# RTD_Sesnor.net
KiCad netlist of a schematic drawn in EAGLE
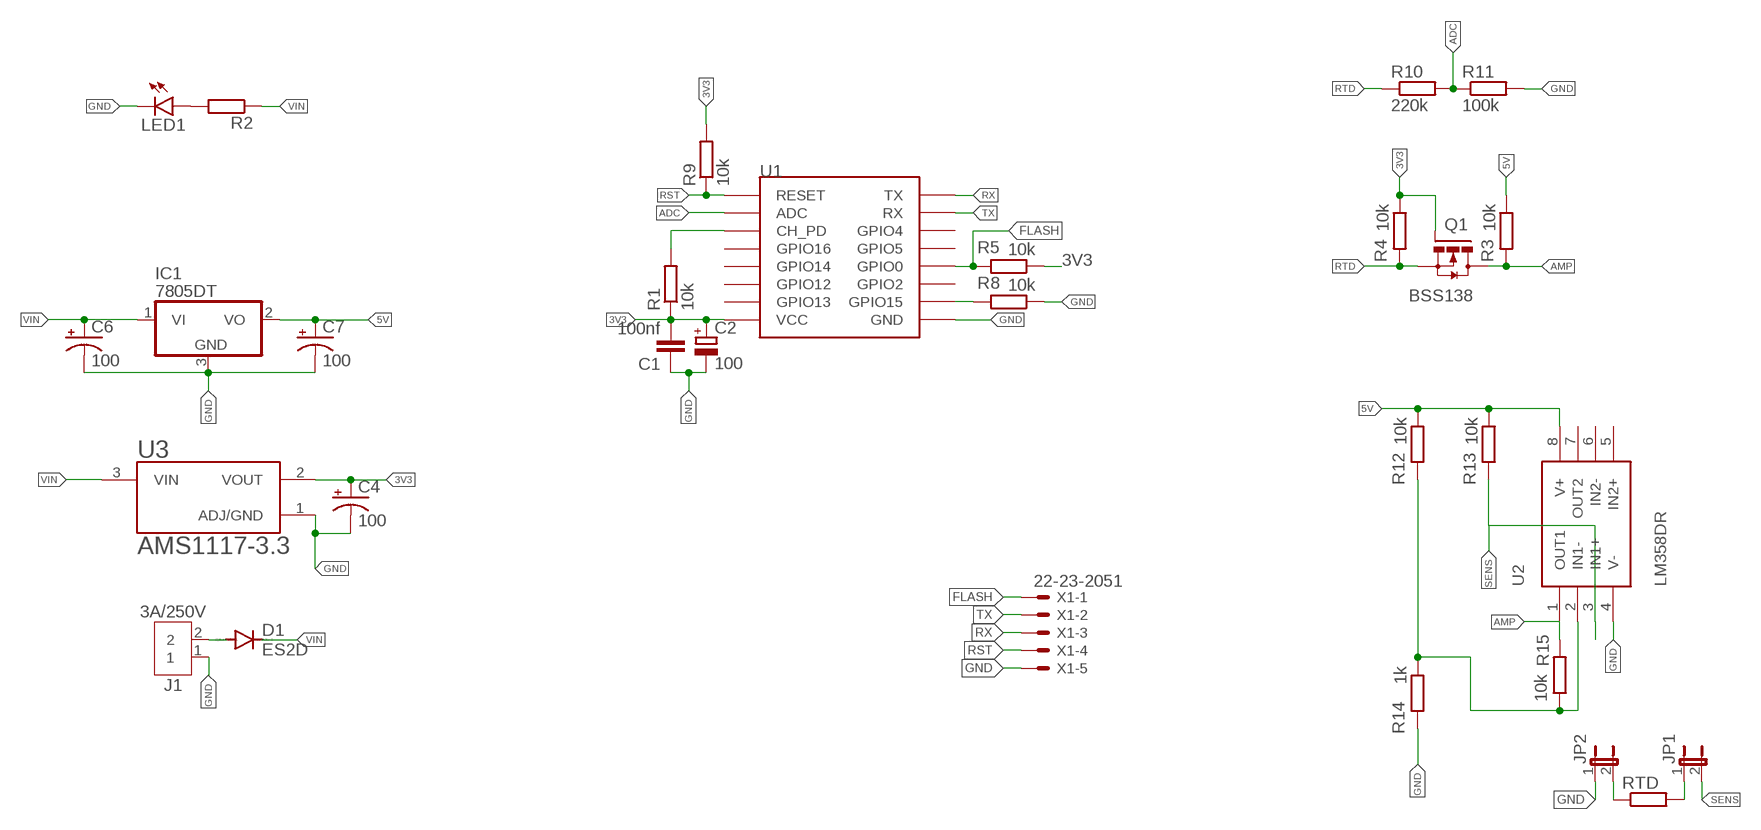
[diagram p0: schematic, sheet 1]

(export (version "E")
  (design (tool "Eeschema 10.0.6"))
  (components
    (comp (ref "C1")
      (value "100nf")
      (footprint "eagle-import:C0805K")
      (libsource (lib "eagle-import") (part "C-EUC0805K"))
    )
    (comp (ref "C2")
      (value "100")
      (footprint "eagle-import:153CLV-0605")
      (libsource (lib "eagle-import") (part "CPOL-EU153CLV-0605"))
    )
    (comp (ref "C4")
      (value "100")
      (footprint "eagle-import:153CLV-0605")
      (libsource (lib "eagle-import") (part "CPOL-US153CLV-0605"))
    )
    (comp (ref "C6")
      (value "100")
      (footprint "eagle-import:153CLV-0605")
      (libsource (lib "eagle-import") (part "CPOL-US153CLV-0605"))
    )
    (comp (ref "C7")
      (value "100")
      (footprint "eagle-import:153CLV-0605")
      (libsource (lib "eagle-import") (part "CPOL-US153CLV-0605"))
    )
    (comp (ref "D1")
      (value "ES2D")
      (footprint "eagle-import:SMB")
      (libsource (lib "eagle-import") (part "ES2D"))
    )
    (comp (ref "IC1")
      (value "7805DT")
      (footprint "eagle-import:TO252")
      (libsource (lib "eagle-import") (part "78DT05"))
    )
    (comp (ref "J1")
      (value "3A/250V")
      (footprint "eagle-import:B2B-XH-A")
      (fields (field (name "MANUFACTURER") "JST (XH CONNECTOR)") (field (name "MPN") "B2B-XH-A"))
      (libsource (lib "eagle-import") (part "B2B-XH-A"))
    )
    (comp (ref "JP1")
      (value "JP1E")
      (footprint "eagle-import:JP1")
      (libsource (lib "eagle-import") (part "JP1E"))
    )
    (comp (ref "JP2")
      (value "JP1E")
      (footprint "eagle-import:JP1")
      (libsource (lib "eagle-import") (part "JP1E"))
    )
    (comp (ref "LED1")
      (value "LED3MM")
      (footprint "eagle-import:LED3MM")
      (libsource (lib "eagle-import") (part "LED3MM"))
    )
    (comp (ref "Q1")
      (value "BSS138")
      (footprint "eagle-import:SOT23-3")
      (fields
        (field (name "DIGIKEY_PART_NUMBER") "BSS138CT-ND")
        (field (name "MANUFACTURER") "ON Semiconductor")
        (field (name "CREATED_BY") "PCBLayout.com")
      )
      (libsource (lib "eagle-import") (part "BSS138"))
    )
    (comp (ref "R1")
      (value "10k")
      (footprint "eagle-import:R1206")
      (libsource (lib "eagle-import") (part "R-EU_R1206"))
    )
    (comp (ref "R2")
      (value "R-EU_R1206")
      (footprint "eagle-import:R1206")
      (libsource (lib "eagle-import") (part "R-EU_R1206"))
    )
    (comp (ref "R3")
      (value "10k")
      (footprint "eagle-import:R1206")
      (libsource (lib "eagle-import") (part "R-EU_R1206"))
    )
    (comp (ref "R4")
      (value "10k")
      (footprint "eagle-import:R1206")
      (libsource (lib "eagle-import") (part "R-EU_R1206"))
    )
    (comp (ref "R5")
      (value "10k")
      (footprint "eagle-import:R1206")
      (libsource (lib "eagle-import") (part "R-EU_R1206"))
    )
    (comp (ref "R8")
      (value "10k")
      (footprint "eagle-import:R1206")
      (libsource (lib "eagle-import") (part "R-EU_R1206"))
    )
    (comp (ref "R9")
      (value "10k")
      (footprint "eagle-import:R1206")
      (libsource (lib "eagle-import") (part "R-EU_R1206"))
    )
    (comp (ref "R10")
      (value "220k")
      (footprint "eagle-import:0204_7")
      (libsource (lib "eagle-import") (part "R-EU_0204/7"))
    )
    (comp (ref "R11")
      (value "100k")
      (footprint "eagle-import:0204_7")
      (libsource (lib "eagle-import") (part "R-EU_0204/7"))
    )
    (comp (ref "R12")
      (value "10k")
      (footprint "eagle-import:R1206")
      (libsource (lib "eagle-import") (part "R-EU_R1206"))
    )
    (comp (ref "R13")
      (value "10k")
      (footprint "eagle-import:R1206")
      (libsource (lib "eagle-import") (part "R-EU_R1206"))
    )
    (comp (ref "R14")
      (value "1k")
      (footprint "eagle-import:R1206")
      (libsource (lib "eagle-import") (part "R-EU_R1206"))
    )
    (comp (ref "R15")
      (value "10k")
      (footprint "eagle-import:R1206")
      (libsource (lib "eagle-import") (part "R-EU_R1206"))
    )
    (comp (ref "RTD")
      (value "R-EU_M0805")
      (footprint "eagle-import:M0805")
      (libsource (lib "eagle-import") (part "R-EU_M0805"))
    )
    (comp (ref "U1")
      (value "ESP12SMD")
      (footprint "eagle-import:ESP12-SMD")
      (libsource (lib "eagle-import") (part "ESP12SMD"))
    )
    (comp (ref "U2")
      (value "LM358DR")
      (footprint "eagle-import:LM358DR")
      (fields
        (field (name "DIGIKEY_PART_NUMBER") "296-1014-1-ND")
        (field (name "MANUFACTURER") "Texas Instruments")
        (field (name "CREATED_BY") "PCBLayout.com")
      )
      (libsource (lib "eagle-import") (part "LM358DR"))
    )
    (comp (ref "U3")
      (value "AMS1117-3.3")
      (footprint "eagle-import:SOT229P700X180-4N")
      (fields (field (name "MF") "Advanced Monolithic Systems"))
      (libsource (lib "eagle-import") (part "AMS1117-3.3"))
    )
    (comp (ref "X1")
      (value "22-23-2051")
      (footprint "eagle-import:22-23-2051")
      (fields (field (name "MF") "MOLEX"))
      (libsource (lib "eagle-import") (part "22-23-2051"))
    )
  )
  (nets
    (net (code "1") (name "3V3") (class "Default")
      (node (ref "C1") (pin "2") (pinfunction "2_2") (pintype "passive"))
      (node (ref "C2") (pin "+") (pinfunction "+_+") (pintype "passive"))
      (node (ref "C4") (pin "+") (pinfunction "+_+") (pintype "passive"))
      (node (ref "Q1") (pin "1") (pinfunction "G_1") (pintype "passive"))
      (node (ref "R1") (pin "1") (pinfunction "1_1") (pintype "passive"))
      (node (ref "R4") (pin "1") (pinfunction "1_1") (pintype "passive"))
      (node (ref "R5") (pin "1") (pinfunction "1_1") (pintype "passive"))
      (node (ref "R9") (pin "2") (pinfunction "2_2") (pintype "passive"))
      (node (ref "U1") (pin "VCC") (pinfunction "VCC_VCC") (pintype "bidirectional"))
      (node (ref "U3") (pin "2") (pinfunction "VOUT_2") (pintype "output"))
    )
    (net (code "2") (name "5V") (class "Default")
      (node (ref "C7") (pin "+") (pinfunction "+_+") (pintype "passive"))
      (node (ref "IC1") (pin "2") (pinfunction "VO_2") (pintype "passive"))
      (node (ref "R12") (pin "1") (pinfunction "1_1") (pintype "passive"))
      (node (ref "R13") (pin "1") (pinfunction "1_1") (pintype "passive"))
      (node (ref "R3") (pin "1") (pinfunction "1_1") (pintype "passive"))
      (node (ref "U2") (pin "8") (pinfunction "V+_8") (pintype "power_in"))
    )
    (net (code "3") (name "ADC") (class "Default")
      (node (ref "R10") (pin "2") (pinfunction "2_2") (pintype "passive"))
      (node (ref "R11") (pin "1") (pinfunction "1_1") (pintype "passive"))
      (node (ref "U1") (pin "ADC") (pinfunction "ADC_ADC") (pintype "bidirectional"))
    )
    (net (code "4") (name "AMP") (class "Default")
      (node (ref "Q1") (pin "3") (pinfunction "D_3") (pintype "passive"))
      (node (ref "R15") (pin "2") (pinfunction "2_2") (pintype "passive"))
      (node (ref "R3") (pin "2") (pinfunction "2_2") (pintype "passive"))
      (node (ref "U2") (pin "1") (pinfunction "OUT1_1") (pintype "output"))
    )
    (net (code "5") (name "FLASH") (class "Default")
      (node (ref "R5") (pin "2") (pinfunction "2_2") (pintype "passive"))
      (node (ref "U1") (pin "GPIO0") (pinfunction "GPIO0_GPIO0") (pintype "bidirectional"))
      (node (ref "X1") (pin "1") (pinfunction "S_1") (pintype "passive"))
    )
    (net (code "6") (name "GND") (class "Default")
      (node (ref "C1") (pin "1") (pinfunction "1_1") (pintype "passive"))
      (node (ref "C2") (pin "-") (pinfunction "-_-") (pintype "passive"))
      (node (ref "C4") (pin "-") (pinfunction "-_-") (pintype "passive"))
      (node (ref "C6") (pin "-") (pinfunction "-_-") (pintype "passive"))
      (node (ref "C7") (pin "-") (pinfunction "-_-") (pintype "passive"))
      (node (ref "IC1") (pin "3") (pinfunction "GND_3") (pintype "passive"))
      (node (ref "J1") (pin "1") (pinfunction "1_1") (pintype "bidirectional"))
      (node (ref "JP2") (pin "1") (pinfunction "1_1") (pintype "passive"))
      (node (ref "LED1") (pin "K") (pinfunction "C_K") (pintype "passive"))
      (node (ref "R11") (pin "2") (pinfunction "2_2") (pintype "passive"))
      (node (ref "R14") (pin "2") (pinfunction "2_2") (pintype "passive"))
      (node (ref "R8") (pin "1") (pinfunction "1_1") (pintype "passive"))
      (node (ref "U1") (pin "GND") (pinfunction "GND_GND") (pintype "bidirectional"))
      (node (ref "U2") (pin "4") (pinfunction "V-_4") (pintype "power_in"))
      (node (ref "U3") (pin "1") (pinfunction "ADJ/GND_1") (pintype "power_in"))
      (node (ref "X1") (pin "5") (pinfunction "S_5") (pintype "passive"))
    )
    (net (code "7") (name "Net-(D1-PadA)") (class "Default")
      (node (ref "D1") (pin "A") (pinfunction "A_A") (pintype "passive"))
      (node (ref "J1") (pin "2") (pinfunction "2_2") (pintype "bidirectional"))
    )
    (net (code "8") (name "Net-(JP1-Pad1)") (class "Default")
      (node (ref "JP1") (pin "1") (pinfunction "1_1") (pintype "passive"))
      (node (ref "RTD") (pin "2") (pinfunction "2_2") (pintype "passive"))
    )
    (net (code "9") (name "Net-(JP2-Pad2)") (class "Default")
      (node (ref "JP2") (pin "2") (pinfunction "2_2") (pintype "passive"))
      (node (ref "RTD") (pin "1") (pinfunction "1_1") (pintype "passive"))
    )
    (net (code "10") (name "Net-(LED1-PadA)") (class "Default")
      (node (ref "LED1") (pin "A") (pinfunction "A_A") (pintype "passive"))
      (node (ref "R2") (pin "2") (pinfunction "2_2") (pintype "passive"))
    )
    (net (code "11") (name "Net-(R1-Pad2)") (class "Default")
      (node (ref "R1") (pin "2") (pinfunction "2_2") (pintype "passive"))
      (node (ref "U1") (pin "CH_PD") (pinfunction "CH_PD_CH_PD") (pintype "bidirectional"))
    )
    (net (code "12") (name "Net-(R8-Pad2)") (class "Default")
      (node (ref "R8") (pin "2") (pinfunction "2_2") (pintype "passive"))
      (node (ref "U1") (pin "GPIO15") (pinfunction "GPIO15_GPIO15") (pintype "bidirectional"))
    )
    (net (code "13") (name "Net-(U2-IN1-)") (class "Default")
      (node (ref "R12") (pin "2") (pinfunction "2_2") (pintype "passive"))
      (node (ref "R14") (pin "1") (pinfunction "1_1") (pintype "passive"))
      (node (ref "R15") (pin "1") (pinfunction "1_1") (pintype "passive"))
      (node (ref "U2") (pin "2") (pinfunction "IN1-_2") (pintype "input"))
    )
    (net (code "14") (name "RST") (class "Default")
      (node (ref "R9") (pin "1") (pinfunction "1_1") (pintype "passive"))
      (node (ref "U1") (pin "RESET") (pinfunction "RESET_RESET") (pintype "bidirectional"))
      (node (ref "X1") (pin "4") (pinfunction "S_4") (pintype "passive"))
    )
    (net (code "15") (name "RTD") (class "Default")
      (node (ref "Q1") (pin "2") (pinfunction "S_2") (pintype "passive"))
      (node (ref "R10") (pin "1") (pinfunction "1_1") (pintype "passive"))
      (node (ref "R4") (pin "2") (pinfunction "2_2") (pintype "passive"))
    )
    (net (code "16") (name "RX") (class "Default")
      (node (ref "U1") (pin "TXD0") (pinfunction "TX_TXD0") (pintype "bidirectional"))
      (node (ref "X1") (pin "3") (pinfunction "S_3") (pintype "passive"))
    )
    (net (code "17") (name "SENS") (class "Default")
      (node (ref "JP1") (pin "2") (pinfunction "2_2") (pintype "passive"))
      (node (ref "R13") (pin "2") (pinfunction "2_2") (pintype "passive"))
      (node (ref "U2") (pin "3") (pinfunction "IN1+_3") (pintype "input"))
    )
    (net (code "18") (name "TX") (class "Default")
      (node (ref "U1") (pin "RXD0") (pinfunction "RX_RXD0") (pintype "bidirectional"))
      (node (ref "X1") (pin "2") (pinfunction "S_2") (pintype "passive"))
    )
    (net (code "19") (name "VIN") (class "Default")
      (node (ref "C6") (pin "+") (pinfunction "+_+") (pintype "passive"))
      (node (ref "D1") (pin "C") (pinfunction "C_C") (pintype "passive"))
      (node (ref "IC1") (pin "1") (pinfunction "VI_1") (pintype "input"))
      (node (ref "R2") (pin "1") (pinfunction "1_1") (pintype "passive"))
      (node (ref "U3") (pin "3") (pinfunction "VIN_3") (pintype "input"))
    )
    (net (code "20") (name "unconnected-(U1-PadGPIO2)") (class "Default")
      (node (ref "U1") (pin "GPIO2") (pinfunction "GPIO2_GPIO2") (pintype "bidirectional"))
    )
    (net (code "21") (name "unconnected-(U1-PadGPIO4)") (class "Default")
      (node (ref "U1") (pin "GPIO4") (pinfunction "GPIO4_GPIO4") (pintype "bidirectional"))
    )
    (net (code "22") (name "unconnected-(U1-PadGPIO5)") (class "Default")
      (node (ref "U1") (pin "GPIO5") (pinfunction "GPIO5_GPIO5") (pintype "bidirectional"))
    )
    (net (code "23") (name "unconnected-(U1-PadGPIO12)") (class "Default")
      (node (ref "U1") (pin "GPIO12") (pinfunction "GPIO12_GPIO12") (pintype "bidirectional"))
    )
    (net (code "24") (name "unconnected-(U1-PadGPIO13)") (class "Default")
      (node (ref "U1") (pin "GPIO13") (pinfunction "GPIO13_GPIO13") (pintype "bidirectional"))
    )
    (net (code "25") (name "unconnected-(U1-PadGPIO14)") (class "Default")
      (node (ref "U1") (pin "GPIO14") (pinfunction "GPIO14_GPIO14") (pintype "bidirectional"))
    )
    (net (code "26") (name "unconnected-(U1-PadGPIO16)") (class "Default")
      (node (ref "U1") (pin "GPIO16") (pinfunction "GPIO16_GPIO16") (pintype "bidirectional"))
    )
    (net (code "27") (name "unconnected-(U2-IN2+-Pad5)") (class "Default")
      (node (ref "U2") (pin "5") (pinfunction "IN2+_5") (pintype "input"))
    )
    (net (code "28") (name "unconnected-(U2-IN2--Pad6)") (class "Default")
      (node (ref "U2") (pin "6") (pinfunction "IN2-_6") (pintype "input"))
    )
    (net (code "29") (name "unconnected-(U2-OUT2-Pad7)") (class "Default")
      (node (ref "U2") (pin "7") (pinfunction "OUT2_7") (pintype "output"))
    )
  )
)
